# gyroscope.net
KiCad netlist of a schematic drawn in Altium Designer
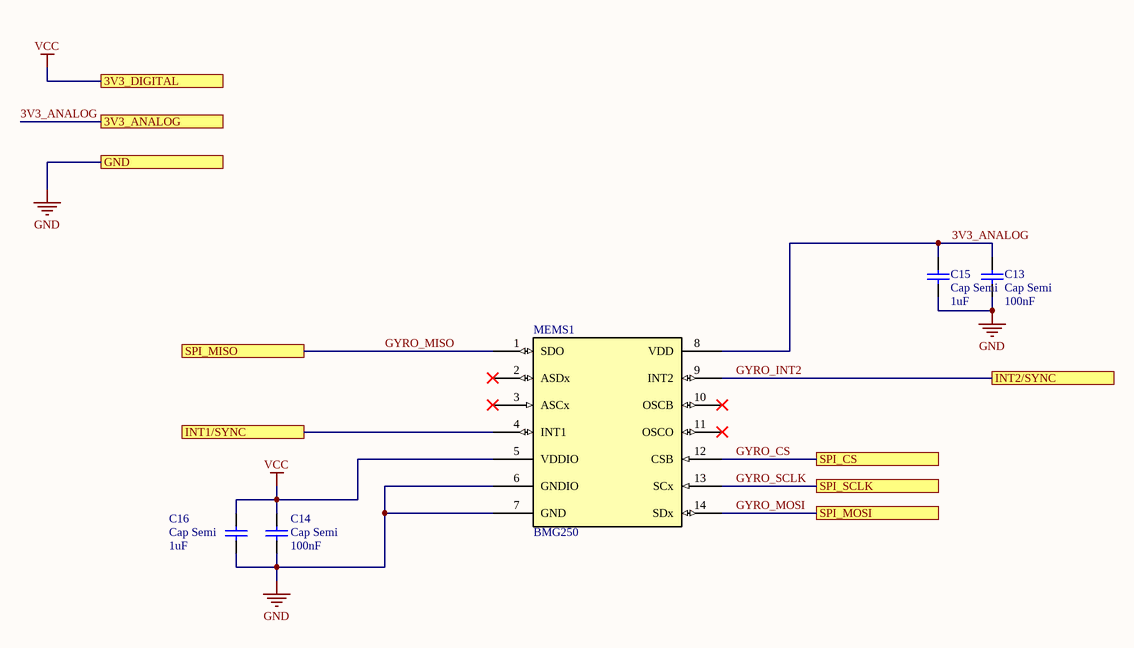
[diagram p0: gyroscope.SchDoc]

(export (version "E")
  (design (tool "Eeschema 10.0.6"))
  (components
    (comp (ref "C13")
      (value "Cap Semi")
      (footprint "C1206")
      (description "Capacitor (Semiconductor SIM Model)")
      (fields (field (name "ALTIUM_VALUE") "100nF") (field (name "PUBLISHER") "Altium Limited"))
      (libsource (lib "Miscellaneous Devices") (part "Cap Semi"))
    )
    (comp (ref "C14")
      (value "Cap Semi")
      (footprint "C1206")
      (description "Capacitor (Semiconductor SIM Model)")
      (fields (field (name "ALTIUM_VALUE") "100nF") (field (name "PUBLISHER") "Altium Limited"))
      (libsource (lib "Miscellaneous Devices") (part "Cap Semi"))
    )
    (comp (ref "C15")
      (value "Cap Semi")
      (footprint "C1210")
      (description "Capacitor (Semiconductor SIM Model)")
      (fields (field (name "ALTIUM_VALUE") "1uF") (field (name "PUBLISHER") "Altium Limited"))
      (libsource (lib "Miscellaneous Devices") (part "Cap Semi"))
    )
    (comp (ref "C16")
      (value "Cap Semi")
      (footprint "C1210")
      (description "Capacitor (Semiconductor SIM Model)")
      (fields (field (name "ALTIUM_VALUE") "1uF") (field (name "PUBLISHER") "Altium Limited"))
      (libsource (lib "Miscellaneous Devices") (part "Cap Semi"))
    )
    (comp (ref "MEMS1")
      (value "BMG250")
      (footprint "LGA14-BOSCH")
      (libsource (lib "RPi_sensor_expansion_board_library") (part "BMG250"))
    )
  )
  (nets
    (net (code "1") (name "/3V3_ANALOG") (class "Default")
      (node (ref "C13") (pin "2") (pinfunction "2_2") (pintype "passive"))
      (node (ref "C15") (pin "2") (pinfunction "2_2") (pintype "passive"))
      (node (ref "MEMS1") (pin "8") (pinfunction "VDD_8") (pintype "power_in"))
    )
    (net (code "2") (name "/GYRO_CS") (class "Default")
      (node (ref "MEMS1") (pin "12") (pinfunction "CSB_12") (pintype "input"))
    )
    (net (code "3") (name "/GYRO_INT2") (class "Default")
      (node (ref "MEMS1") (pin "9") (pinfunction "INT2_9") (pintype "bidirectional"))
    )
    (net (code "4") (name "/GYRO_MISO") (class "Default")
      (node (ref "MEMS1") (pin "1") (pinfunction "SDO_1") (pintype "bidirectional"))
    )
    (net (code "5") (name "/GYRO_MOSI") (class "Default")
      (node (ref "MEMS1") (pin "14") (pinfunction "SDx_14") (pintype "bidirectional"))
    )
    (net (code "6") (name "/GYRO_SCLK") (class "Default")
      (node (ref "MEMS1") (pin "13") (pinfunction "SCx_13") (pintype "input"))
    )
    (net (code "7") (name "/INT1{slash}SYNC") (class "Default")
      (node (ref "MEMS1") (pin "4") (pinfunction "INT1_4") (pintype "bidirectional"))
    )
    (net (code "8") (name "GND") (class "Default")
      (node (ref "C13") (pin "1") (pinfunction "1_1") (pintype "passive"))
      (node (ref "C14") (pin "1") (pinfunction "1_1") (pintype "passive"))
      (node (ref "C15") (pin "1") (pinfunction "1_1") (pintype "passive"))
      (node (ref "C16") (pin "1") (pinfunction "1_1") (pintype "passive"))
      (node (ref "MEMS1") (pin "6") (pinfunction "GNDIO_6") (pintype "power_in"))
      (node (ref "MEMS1") (pin "7") (pinfunction "GND_7") (pintype "power_in"))
    )
    (net (code "9") (name "VCC") (class "Default")
      (node (ref "C14") (pin "2") (pinfunction "2_2") (pintype "passive"))
      (node (ref "C16") (pin "2") (pinfunction "2_2") (pintype "passive"))
      (node (ref "MEMS1") (pin "5") (pinfunction "VDDIO_5") (pintype "power_in"))
    )
    (net (code "10") (name "unconnected-(MEMS1-ASCx-Pad3)") (class "Default")
      (node (ref "MEMS1") (pin "3") (pinfunction "ASCx_3") (pintype "input+no_connect"))
    )
    (net (code "11") (name "unconnected-(MEMS1-ASDx-Pad2)") (class "Default")
      (node (ref "MEMS1") (pin "2") (pinfunction "ASDx_2") (pintype "bidirectional+no_connect"))
    )
    (net (code "12") (name "unconnected-(MEMS1-OSCB-Pad10)") (class "Default")
      (node (ref "MEMS1") (pin "10") (pinfunction "OSCB_10") (pintype "bidirectional+no_connect"))
    )
    (net (code "13") (name "unconnected-(MEMS1-OSCO-Pad11)") (class "Default")
      (node (ref "MEMS1") (pin "11") (pinfunction "OSCO_11") (pintype "bidirectional+no_connect"))
    )
  )
)
